# er_s_t.net
KiCad netlist of a schematic drawn in EAGLE
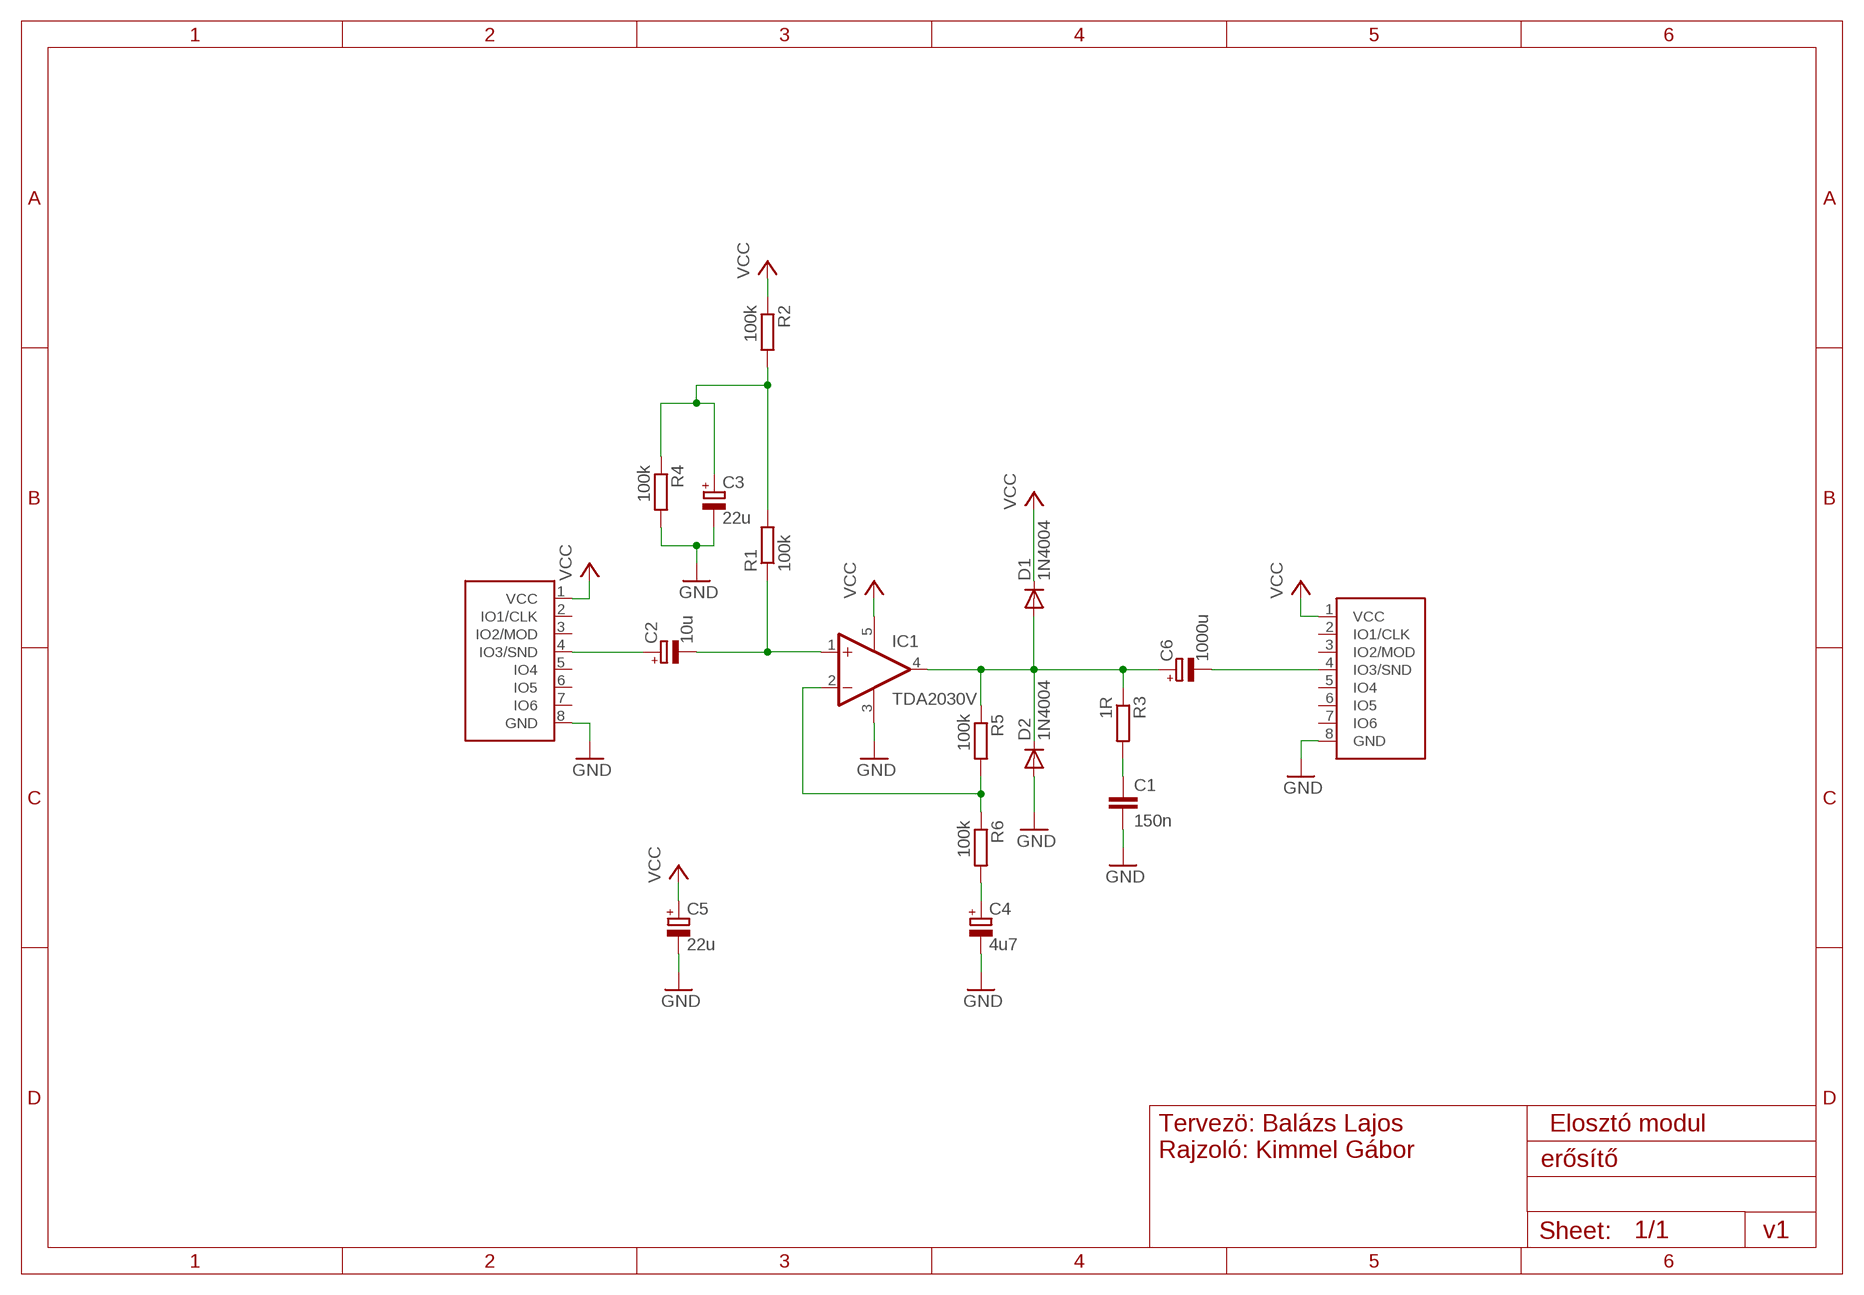
[diagram p0: schematic, sheet 1]

(export (version "E")
  (design (tool "Eeschema 10.0.6"))
  (components
    (comp (ref "C1")
      (value "150n")
      (footprint "eagle-import:C075-032X103")
      (libsource (lib "eagle-import") (part "C-EU075-032X103"))
    )
    (comp (ref "C2")
      (value "10u")
      (footprint "eagle-import:E2,5-7")
      (libsource (lib "eagle-import") (part "CPOL-EUE2.5-7"))
    )
    (comp (ref "C3")
      (value "22u")
      (footprint "eagle-import:E2,5-7")
      (libsource (lib "eagle-import") (part "CPOL-EUE2.5-7"))
    )
    (comp (ref "C4")
      (value "4u7")
      (footprint "eagle-import:E2,5-7")
      (libsource (lib "eagle-import") (part "CPOL-EUE2.5-7"))
    )
    (comp (ref "C5")
      (value "22u")
      (footprint "eagle-import:E2,5-7")
      (libsource (lib "eagle-import") (part "CPOL-EUE2.5-7"))
    )
    (comp (ref "C6")
      (value "1000u")
      (footprint "eagle-import:E3,5-8")
      (libsource (lib "eagle-import") (part "CPOL-EUE3.5-8"))
    )
    (comp (ref "D1")
      (value "1N4004")
      (footprint "eagle-import:DO41-10")
      (libsource (lib "eagle-import") (part "1N4004"))
    )
    (comp (ref "D2")
      (value "1N4004")
      (footprint "eagle-import:DO41-10")
      (libsource (lib "eagle-import") (part "1N4004"))
    )
    (comp (ref "IC1")
      (value "TDA2030V")
      (footprint "eagle-import:CB360")
      (libsource (lib "eagle-import") (part "TDA2030V"))
    )
    (comp (ref "R1")
      (value "100k")
      (footprint "eagle-import:0309_12")
      (libsource (lib "eagle-import") (part "R-EU_0309/12"))
    )
    (comp (ref "R2")
      (value "100k")
      (footprint "eagle-import:0309_12")
      (libsource (lib "eagle-import") (part "R-EU_0309/12"))
    )
    (comp (ref "R3")
      (value "1R")
      (footprint "eagle-import:0309_12")
      (libsource (lib "eagle-import") (part "R-EU_0309/12"))
    )
    (comp (ref "R4")
      (value "100k")
      (footprint "eagle-import:0309_12")
      (libsource (lib "eagle-import") (part "R-EU_0309/12"))
    )
    (comp (ref "R5")
      (value "100k")
      (footprint "eagle-import:0309_12")
      (libsource (lib "eagle-import") (part "R-EU_0309/12"))
    )
    (comp (ref "R6")
      (value "100k")
      (footprint "eagle-import:0309_12")
      (libsource (lib "eagle-import") (part "R-EU_0309/12"))
    )
    (comp (ref "U$1")
      (value "GANZ-CONNECTOR")
      (footprint "eagle-import:FE08W")
      (libsource (lib "eagle-import") (part "GANZ-CONNECTOR"))
    )
    (comp (ref "U$2")
      (value "GANZ-CONNECTOR-OUT")
      (footprint "eagle-import:MA08-1W")
      (libsource (lib "eagle-import") (part "GANZ-CONNECTOR-OUT"))
    )
  )
  (nets
    (net (code "1") (name "GND") (class "Default")
      (node (ref "C1") (pin "2") (pinfunction "2_2") (pintype "passive"))
      (node (ref "C3") (pin "-") (pinfunction "-_-") (pintype "passive"))
      (node (ref "C4") (pin "-") (pinfunction "-_-") (pintype "passive"))
      (node (ref "C5") (pin "-") (pinfunction "-_-") (pintype "passive"))
      (node (ref "D2") (pin "A") (pinfunction "A_A") (pintype "passive"))
      (node (ref "IC1") (pin "3") (pinfunction "GND_3") (pintype "power_in"))
      (node (ref "R4") (pin "2") (pinfunction "2_2") (pintype "passive"))
      (node (ref "U$1") (pin "8") (pinfunction "GND_8") (pintype "bidirectional"))
      (node (ref "U$2") (pin "8") (pinfunction "GND_8") (pintype "bidirectional"))
    )
    (net (code "2") (name "Net-(C1-Pad1)") (class "Default")
      (node (ref "C1") (pin "1") (pinfunction "1_1") (pintype "passive"))
      (node (ref "R3") (pin "2") (pinfunction "2_2") (pintype "passive"))
    )
    (net (code "3") (name "Net-(C3-Pad+)") (class "Default")
      (node (ref "C3") (pin "+") (pinfunction "+_+") (pintype "passive"))
      (node (ref "R1") (pin "2") (pinfunction "2_2") (pintype "passive"))
      (node (ref "R2") (pin "2") (pinfunction "2_2") (pintype "passive"))
      (node (ref "R4") (pin "1") (pinfunction "1_1") (pintype "passive"))
    )
    (net (code "4") (name "Net-(C4-Pad+)") (class "Default")
      (node (ref "C4") (pin "+") (pinfunction "+_+") (pintype "passive"))
      (node (ref "R6") (pin "2") (pinfunction "2_2") (pintype "passive"))
    )
    (net (code "5") (name "Net-(IC1-+IN)") (class "Default")
      (node (ref "C2") (pin "-") (pinfunction "-_-") (pintype "passive"))
      (node (ref "IC1") (pin "1") (pinfunction "+IN_1") (pintype "input"))
      (node (ref "R1") (pin "1") (pinfunction "1_1") (pintype "passive"))
    )
    (net (code "6") (name "Net-(IC1--IN)") (class "Default")
      (node (ref "IC1") (pin "2") (pinfunction "-IN_2") (pintype "input"))
      (node (ref "R5") (pin "2") (pinfunction "2_2") (pintype "passive"))
      (node (ref "R6") (pin "1") (pinfunction "1_1") (pintype "passive"))
    )
    (net (code "7") (name "Net-(IC1-OUT)") (class "Default")
      (node (ref "C6") (pin "+") (pinfunction "+_+") (pintype "passive"))
      (node (ref "D1") (pin "A") (pinfunction "A_A") (pintype "passive"))
      (node (ref "D2") (pin "C") (pinfunction "C_C") (pintype "passive"))
      (node (ref "IC1") (pin "4") (pinfunction "OUT_4") (pintype "output"))
      (node (ref "R3") (pin "1") (pinfunction "1_1") (pintype "passive"))
      (node (ref "R5") (pin "1") (pinfunction "1_1") (pintype "passive"))
    )
    (net (code "8") (name "Net-(U$1-IO3{slash}SND)") (class "Default")
      (node (ref "C2") (pin "+") (pinfunction "+_+") (pintype "passive"))
      (node (ref "U$1") (pin "4") (pinfunction "IO3/SND_4") (pintype "bidirectional"))
    )
    (net (code "9") (name "Net-(U$2-IO3{slash}SND)") (class "Default")
      (node (ref "C6") (pin "-") (pinfunction "-_-") (pintype "passive"))
      (node (ref "U$2") (pin "4") (pinfunction "IO3/SND_4") (pintype "bidirectional"))
    )
    (net (code "10") (name "VCC") (class "Default")
      (node (ref "C5") (pin "+") (pinfunction "+_+") (pintype "passive"))
      (node (ref "D1") (pin "C") (pinfunction "C_C") (pintype "passive"))
      (node (ref "IC1") (pin "5") (pinfunction "V+_5") (pintype "power_in"))
      (node (ref "R2") (pin "1") (pinfunction "1_1") (pintype "passive"))
      (node (ref "U$1") (pin "1") (pinfunction "VCC_1") (pintype "bidirectional"))
      (node (ref "U$2") (pin "1") (pinfunction "VCC_1") (pintype "bidirectional"))
    )
    (net (code "11") (name "unconnected-(U$1-IO1{slash}CLK-Pad2)") (class "Default")
      (node (ref "U$1") (pin "2") (pinfunction "IO1/CLK_2") (pintype "bidirectional"))
    )
    (net (code "12") (name "unconnected-(U$1-IO2{slash}MOD-Pad3)") (class "Default")
      (node (ref "U$1") (pin "3") (pinfunction "IO2/MOD_3") (pintype "bidirectional"))
    )
    (net (code "13") (name "unconnected-(U$1-IO4-Pad5)") (class "Default")
      (node (ref "U$1") (pin "5") (pinfunction "IO4_5") (pintype "bidirectional"))
    )
    (net (code "14") (name "unconnected-(U$1-IO5-Pad6)") (class "Default")
      (node (ref "U$1") (pin "6") (pinfunction "IO5_6") (pintype "bidirectional"))
    )
    (net (code "15") (name "unconnected-(U$1-IO6-Pad7)") (class "Default")
      (node (ref "U$1") (pin "7") (pinfunction "IO6_7") (pintype "bidirectional"))
    )
    (net (code "16") (name "unconnected-(U$2-IO1{slash}CLK-Pad2)") (class "Default")
      (node (ref "U$2") (pin "2") (pinfunction "IO1/CLK_2") (pintype "bidirectional"))
    )
    (net (code "17") (name "unconnected-(U$2-IO2{slash}MOD-Pad3)") (class "Default")
      (node (ref "U$2") (pin "3") (pinfunction "IO2/MOD_3") (pintype "bidirectional"))
    )
    (net (code "18") (name "unconnected-(U$2-IO4-Pad5)") (class "Default")
      (node (ref "U$2") (pin "5") (pinfunction "IO4_5") (pintype "bidirectional"))
    )
    (net (code "19") (name "unconnected-(U$2-IO5-Pad6)") (class "Default")
      (node (ref "U$2") (pin "6") (pinfunction "IO5_6") (pintype "bidirectional"))
    )
    (net (code "20") (name "unconnected-(U$2-IO6-Pad7)") (class "Default")
      (node (ref "U$2") (pin "7") (pinfunction "IO6_7") (pintype "bidirectional"))
    )
  )
)
